# Sheet1.net
KiCad netlist of a schematic drawn in Altium Designer
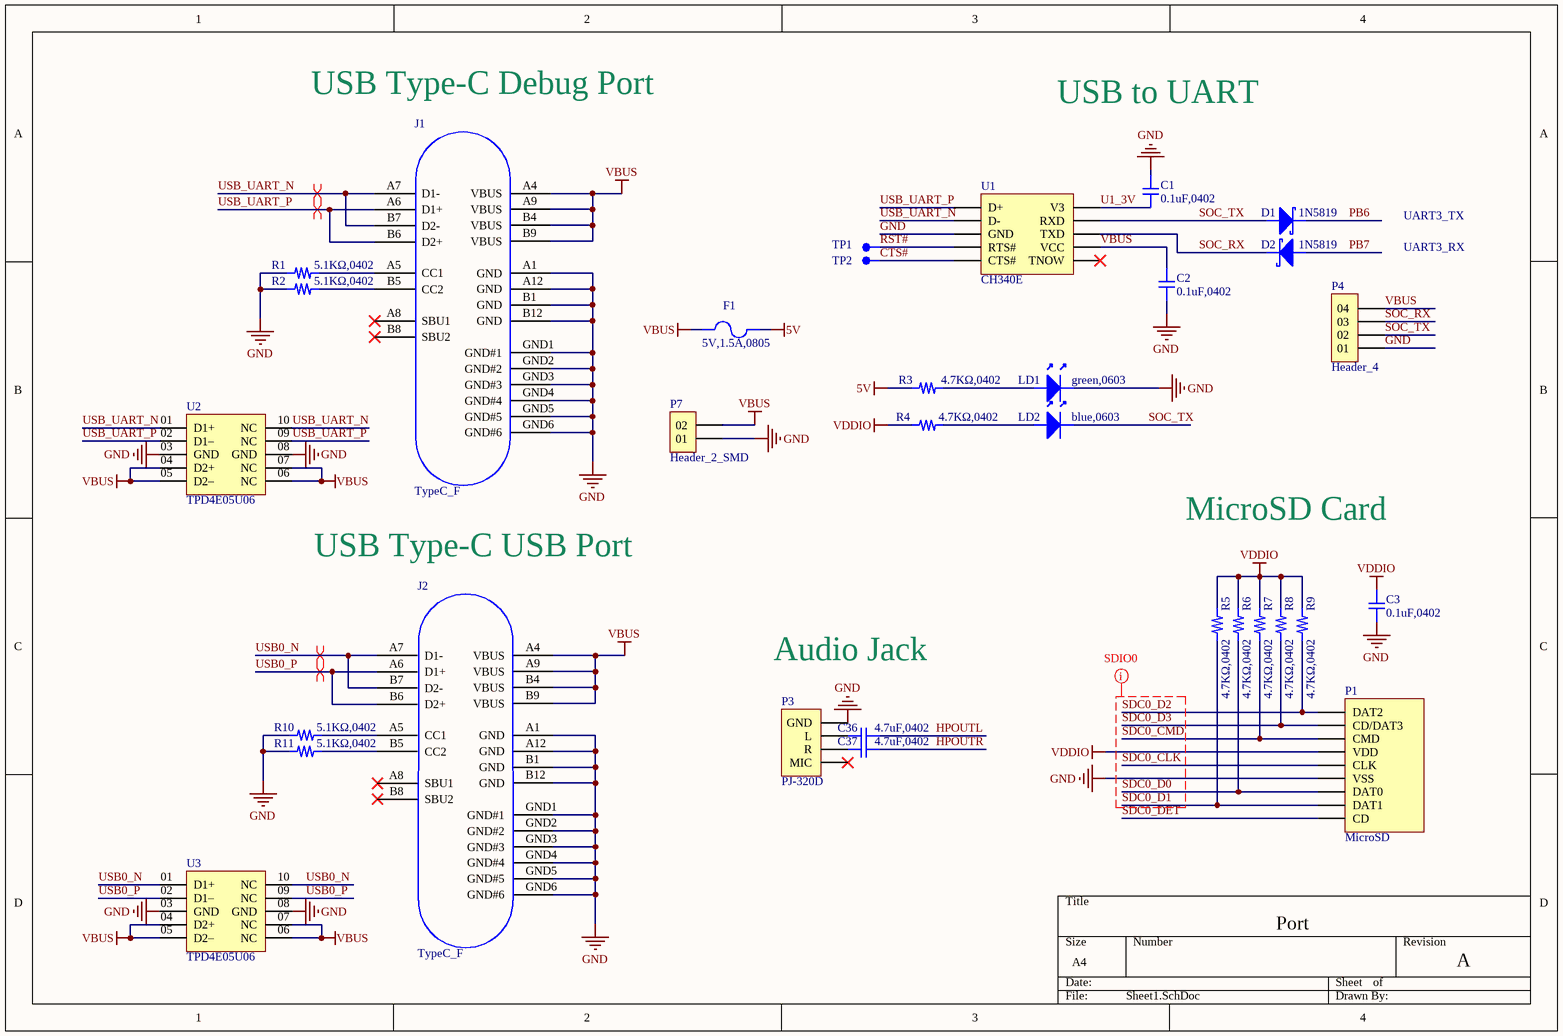
[diagram p0: Sheet1.SchDoc]

(export (version "E")
  (design (tool "Eeschema 10.0.6"))
  (components
    (comp (ref "C1") (value "0.1uF,0402") (footprint "C0402") (libsource (lib "myLib1") (part "Cap")))
    (comp (ref "C2") (value "0.1uF,0402") (footprint "C0402") (libsource (lib "myLib1") (part "Cap")))
    (comp (ref "C3") (value "0.1uF,0402") (footprint "C0402") (libsource (lib "myLib1") (part "Cap")))
    (comp (ref "C36") (value "4.7uF,0402") (footprint "C0402") (libsource (lib "myLib1") (part "Cap")))
    (comp (ref "C37") (value "4.7uF,0402") (footprint "C0402") (libsource (lib "myLib1") (part "Cap")))
    (comp (ref "D1")
      (value "1N5819")
      (footprint "SOD-323")
      (libsource (lib "myLib1") (part "Diode - Schottky"))
    )
    (comp (ref "D2")
      (value "1N5819")
      (footprint "SOD-323")
      (libsource (lib "myLib1") (part "Diode - Schottky"))
    )
    (comp (ref "F1") (value "5V,1.5A,0805") (footprint "F0805") (libsource (lib "myLib1") (part "Fuse")))
    (comp (ref "J1")
      (value "TypeC_F")
      (footprint "Type-C_16P_F_0.5_DIP")
      (description "Female SMD Connector")
      (libsource (lib "myLib1") (part "Type-C_16P_F_0.5"))
    )
    (comp (ref "J2")
      (value "TypeC_F")
      (footprint "Type-C_16P_F_0.5_DIP")
      (description "Female SMD Connector")
      (libsource (lib "myLib1") (part "Type-C_16P_F_0.5"))
    )
    (comp (ref "LD1")
      (value "green,0603")
      (footprint "LED0603")
      (libsource (lib "myLib1") (part "Diode - LED"))
    )
    (comp (ref "LD2")
      (value "blue,0603")
      (footprint "LED0603")
      (libsource (lib "myLib1") (part "Diode - LED"))
    )
    (comp (ref "P1") (value "MicroSD") (footprint "MicroSD") (libsource (lib "myLib1") (part "MicroSD")))
    (comp (ref "P3")
      (value "PJ-320D")
      (footprint "PJ-320D")
      (description "Audio jack")
      (libsource (lib "myLib1") (part "PJ-320D"))
    )
    (comp (ref "P4")
      (value "Header_4")
      (footprint "HEADER_4_SMD")
      (libsource (lib "myLib1") (part "Header_4"))
    )
    (comp (ref "P7")
      (value "Header_2_SMD")
      (footprint "HEADER_2_SMD")
      (libsource (lib "myLib1") (part "Header_2"))
    )
    (comp (ref "R1") (value "5.1KΩ,0402") (footprint "R0402") (libsource (lib "myLib1") (part "Res")))
    (comp (ref "R2") (value "5.1KΩ,0402") (footprint "R0402") (libsource (lib "myLib1") (part "Res")))
    (comp (ref "R3") (value "4.7KΩ,0402") (footprint "R0402") (libsource (lib "myLib1") (part "Res")))
    (comp (ref "R4") (value "4.7KΩ,0402") (footprint "R0402") (libsource (lib "myLib1") (part "Res")))
    (comp (ref "R5") (value "4.7KΩ,0402") (footprint "R0402") (libsource (lib "myLib1") (part "Res")))
    (comp (ref "R6") (value "4.7KΩ,0402") (footprint "R0402") (libsource (lib "myLib1") (part "Res")))
    (comp (ref "R7") (value "4.7KΩ,0402") (footprint "R0402") (libsource (lib "myLib1") (part "Res")))
    (comp (ref "R8") (value "4.7KΩ,0402") (footprint "R0402") (libsource (lib "myLib1") (part "Res")))
    (comp (ref "R9") (value "4.7KΩ,0402") (footprint "R0402") (libsource (lib "myLib1") (part "Res")))
    (comp (ref "R10") (value "5.1KΩ,0402") (footprint "R0402") (libsource (lib "myLib1") (part "Res")))
    (comp (ref "R11") (value "5.1KΩ,0402") (footprint "R0402") (libsource (lib "myLib1") (part "Res")))
    (comp (ref "TP1") (value "TP") (footprint "TP") (libsource (lib "myLib1") (part "TP")))
    (comp (ref "TP2") (value "TP") (footprint "TP") (libsource (lib "myLib1") (part "TP")))
    (comp (ref "U1") (value "CH340E") (footprint "MSOP-10") (libsource (lib "myLib1") (part "CH340E")))
    (comp (ref "U2")
      (value "TPD4E05U06")
      (footprint "USON-10")
      (libsource (lib "myLib1") (part "TPD4E05U06"))
    )
    (comp (ref "U3")
      (value "TPD4E05U06")
      (footprint "USON-10")
      (libsource (lib "myLib1") (part "TPD4E05U06"))
    )
  )
  (nets
    (net (code "1") (name "/CTS#") (class "Default")
      (node (ref "TP2") (pin "01") (pintype "passive"))
      (node (ref "U1") (pin "05") (pinfunction "CTS#_05") (pintype "passive"))
    )
    (net (code "2") (name "/HPOUTL") (class "Default") (node (ref "C36") (pin "01") (pintype "passive")))
    (net (code "3") (name "/HPOUTR") (class "Default") (node (ref "C37") (pin "01") (pintype "passive")))
    (net (code "4") (name "/PB6") (class "Default") (node (ref "D1") (pin "02") (pintype "passive")))
    (net (code "5") (name "/PB7") (class "Default") (node (ref "D2") (pin "01") (pintype "passive")))
    (net (code "6") (name "/RST#") (class "Default")
      (node (ref "TP1") (pin "01") (pintype "passive"))
      (node (ref "U1") (pin "04") (pinfunction "RTS#_04") (pintype "passive"))
    )
    (net (code "7") (name "/SDC0_CLK") (class "Default")
      (node (ref "P1") (pin "05") (pinfunction "CLK_05") (pintype "passive"))
    )
    (net (code "8") (name "/SDC0_CMD") (class "Default")
      (node (ref "P1") (pin "03") (pinfunction "CMD_03") (pintype "passive"))
      (node (ref "R7") (pin "01") (pintype "passive"))
    )
    (net (code "9") (name "/SDC0_D0") (class "Default")
      (node (ref "P1") (pin "07") (pinfunction "DAT0_07") (pintype "passive"))
      (node (ref "R6") (pin "01") (pintype "passive"))
    )
    (net (code "10") (name "/SDC0_D1") (class "Default")
      (node (ref "P1") (pin "08") (pinfunction "DAT1_08") (pintype "passive"))
      (node (ref "R5") (pin "01") (pintype "passive"))
    )
    (net (code "11") (name "/SDC0_D2") (class "Default")
      (node (ref "P1") (pin "01") (pinfunction "DAT2_01") (pintype "passive"))
      (node (ref "R9") (pin "01") (pintype "passive"))
    )
    (net (code "12") (name "/SDC0_D3") (class "Default")
      (node (ref "P1") (pin "02") (pinfunction "CD/DAT3_02") (pintype "passive"))
      (node (ref "R8") (pin "01") (pintype "passive"))
    )
    (net (code "13") (name "/SDC0_DET") (class "Default")
      (node (ref "P1") (pin "09") (pinfunction "CD_09") (pintype "passive"))
    )
    (net (code "14") (name "/SOC_RX") (class "Default")
      (node (ref "D2") (pin "02") (pintype "passive"))
      (node (ref "P4") (pin "03") (pinfunction "03_03") (pintype "passive"))
      (node (ref "U1") (pin "08") (pinfunction "TXD_08") (pintype "passive"))
    )
    (net (code "15") (name "/SOC_TX") (class "Default")
      (node (ref "D1") (pin "01") (pintype "passive"))
      (node (ref "LD2") (pin "02") (pintype "passive"))
      (node (ref "P4") (pin "02") (pinfunction "02_02") (pintype "passive"))
      (node (ref "U1") (pin "09") (pinfunction "RXD_09") (pintype "passive"))
    )
    (net (code "16") (name "/U1_3V") (class "Default")
      (node (ref "C1") (pin "01") (pintype "passive"))
      (node (ref "U1") (pin "10") (pinfunction "V3_10") (pintype "passive"))
    )
    (net (code "17") (name "/USB0_N") (class "Default")
      (node (ref "J2") (pin "A7") (pinfunction "D1-_A7") (pintype "passive"))
      (node (ref "J2") (pin "B7") (pinfunction "D2-_B7") (pintype "passive"))
      (node (ref "U3") (pin "01") (pinfunction "D1+_01") (pintype "passive"))
      (node (ref "U3") (pin "10") (pinfunction "NC_10") (pintype "passive"))
    )
    (net (code "18") (name "/USB0_P") (class "Default")
      (node (ref "J2") (pin "A6") (pinfunction "D1+_A6") (pintype "passive"))
      (node (ref "J2") (pin "B6") (pinfunction "D2+_B6") (pintype "passive"))
      (node (ref "U3") (pin "02") (pinfunction "D1–_02") (pintype "passive"))
      (node (ref "U3") (pin "09") (pinfunction "NC_09") (pintype "passive"))
    )
    (net (code "19") (name "/USB_UART_N") (class "Default")
      (node (ref "J1") (pin "A7") (pinfunction "D1-_A7") (pintype "passive"))
      (node (ref "J1") (pin "B7") (pinfunction "D2-_B7") (pintype "passive"))
      (node (ref "U1") (pin "02") (pinfunction "D-_02") (pintype "passive"))
      (node (ref "U2") (pin "01") (pinfunction "D1+_01") (pintype "passive"))
      (node (ref "U2") (pin "10") (pinfunction "NC_10") (pintype "passive"))
    )
    (net (code "20") (name "/USB_UART_P") (class "Default")
      (node (ref "J1") (pin "A6") (pinfunction "D1+_A6") (pintype "passive"))
      (node (ref "J1") (pin "B6") (pinfunction "D2+_B6") (pintype "passive"))
      (node (ref "U1") (pin "01") (pinfunction "D+_01") (pintype "passive"))
      (node (ref "U2") (pin "02") (pinfunction "D1–_02") (pintype "passive"))
      (node (ref "U2") (pin "09") (pinfunction "NC_09") (pintype "passive"))
    )
    (net (code "21") (name "5V") (class "Default")
      (node (ref "F1") (pin "02") (pintype "passive"))
      (node (ref "R3") (pin "01") (pintype "passive"))
    )
    (net (code "22") (name "GND") (class "Default")
      (node (ref "C1") (pin "02") (pintype "passive"))
      (node (ref "C2") (pin "01") (pintype "passive"))
      (node (ref "C3") (pin "01") (pintype "passive"))
      (node (ref "J1") (pin "A1") (pinfunction "GND_A1") (pintype "power_in"))
      (node (ref "J1") (pin "A12") (pinfunction "GND_A12") (pintype "power_in"))
      (node (ref "J1") (pin "B1") (pinfunction "GND_B1") (pintype "power_in"))
      (node (ref "J1") (pin "B12") (pinfunction "GND_B12") (pintype "power_in"))
      (node (ref "J1") (pin "GND1") (pinfunction "GND#1_GND1") (pintype "passive"))
      (node (ref "J1") (pin "GND2") (pinfunction "GND#2_GND2") (pintype "passive"))
      (node (ref "J1") (pin "GND3") (pinfunction "GND#3_GND3") (pintype "passive"))
      (node (ref "J1") (pin "GND4") (pinfunction "GND#4_GND4") (pintype "passive"))
      (node (ref "J1") (pin "GND5") (pinfunction "GND#5_GND5") (pintype "passive"))
      (node (ref "J1") (pin "GND6") (pinfunction "GND#6_GND6") (pintype "passive"))
      (node (ref "J2") (pin "A1") (pinfunction "GND_A1") (pintype "power_in"))
      (node (ref "J2") (pin "A12") (pinfunction "GND_A12") (pintype "power_in"))
      (node (ref "J2") (pin "B1") (pinfunction "GND_B1") (pintype "power_in"))
      (node (ref "J2") (pin "B12") (pinfunction "GND_B12") (pintype "power_in"))
      (node (ref "J2") (pin "GND1") (pinfunction "GND#1_GND1") (pintype "passive"))
      (node (ref "J2") (pin "GND2") (pinfunction "GND#2_GND2") (pintype "passive"))
      (node (ref "J2") (pin "GND3") (pinfunction "GND#3_GND3") (pintype "passive"))
      (node (ref "J2") (pin "GND4") (pinfunction "GND#4_GND4") (pintype "passive"))
      (node (ref "J2") (pin "GND5") (pinfunction "GND#5_GND5") (pintype "passive"))
      (node (ref "J2") (pin "GND6") (pinfunction "GND#6_GND6") (pintype "passive"))
      (node (ref "LD1") (pin "02") (pintype "passive"))
      (node (ref "P1") (pin "06") (pinfunction "VSS_06") (pintype "passive"))
      (node (ref "P3") (pin "01") (pinfunction "GND_01") (pintype "passive"))
      (node (ref "P4") (pin "01") (pinfunction "01_01") (pintype "passive"))
      (node (ref "P7") (pin "01") (pinfunction "01_01") (pintype "passive"))
      (node (ref "R1") (pin "01") (pintype "passive"))
      (node (ref "R10") (pin "01") (pintype "passive"))
      (node (ref "R11") (pin "01") (pintype "passive"))
      (node (ref "R2") (pin "01") (pintype "passive"))
      (node (ref "U1") (pin "03") (pinfunction "GND_03") (pintype "passive"))
      (node (ref "U2") (pin "03") (pinfunction "GND_03") (pintype "passive"))
      (node (ref "U2") (pin "08") (pinfunction "GND_08") (pintype "passive"))
      (node (ref "U3") (pin "03") (pinfunction "GND_03") (pintype "passive"))
      (node (ref "U3") (pin "08") (pinfunction "GND_08") (pintype "passive"))
    )
    (net (code "23") (name "Net-(J1-CC1)") (class "Default")
      (node (ref "J1") (pin "A5") (pinfunction "CC1_A5") (pintype "passive"))
      (node (ref "R1") (pin "02") (pintype "passive"))
    )
    (net (code "24") (name "Net-(J1-CC2)") (class "Default")
      (node (ref "J1") (pin "B5") (pinfunction "CC2_B5") (pintype "passive"))
      (node (ref "R2") (pin "02") (pintype "passive"))
    )
    (net (code "25") (name "Net-(J2-CC1)") (class "Default")
      (node (ref "J2") (pin "A5") (pinfunction "CC1_A5") (pintype "passive"))
      (node (ref "R10") (pin "02") (pintype "passive"))
    )
    (net (code "26") (name "Net-(J2-CC2)") (class "Default")
      (node (ref "J2") (pin "B5") (pinfunction "CC2_B5") (pintype "passive"))
      (node (ref "R11") (pin "02") (pintype "passive"))
    )
    (net (code "27") (name "Net-(LD1-Pad01)") (class "Default")
      (node (ref "LD1") (pin "01") (pintype "passive"))
      (node (ref "R3") (pin "02") (pintype "passive"))
    )
    (net (code "28") (name "Net-(LD2-Pad01)") (class "Default")
      (node (ref "LD2") (pin "01") (pintype "passive"))
      (node (ref "R4") (pin "02") (pintype "passive"))
    )
    (net (code "29") (name "Net-(P3-L)") (class "Default")
      (node (ref "C36") (pin "02") (pintype "passive"))
      (node (ref "P3") (pin "04") (pinfunction "L_04") (pintype "passive"))
    )
    (net (code "30") (name "Net-(P3-R)") (class "Default")
      (node (ref "C37") (pin "02") (pintype "passive"))
      (node (ref "P3") (pin "03") (pinfunction "R_03") (pintype "passive"))
    )
    (net (code "31") (name "VBUS") (class "Default")
      (node (ref "C2") (pin "02") (pintype "passive"))
      (node (ref "F1") (pin "01") (pintype "passive"))
      (node (ref "J1") (pin "A4") (pinfunction "VBUS_A4") (pintype "power_in"))
      (node (ref "J1") (pin "A9") (pinfunction "VBUS_A9") (pintype "power_in"))
      (node (ref "J1") (pin "B4") (pinfunction "VBUS_B4") (pintype "power_in"))
      (node (ref "J1") (pin "B9") (pinfunction "VBUS_B9") (pintype "power_in"))
      (node (ref "J2") (pin "A4") (pinfunction "VBUS_A4") (pintype "power_in"))
      (node (ref "J2") (pin "A9") (pinfunction "VBUS_A9") (pintype "power_in"))
      (node (ref "J2") (pin "B4") (pinfunction "VBUS_B4") (pintype "power_in"))
      (node (ref "J2") (pin "B9") (pinfunction "VBUS_B9") (pintype "power_in"))
      (node (ref "P4") (pin "04") (pinfunction "04_04") (pintype "passive"))
      (node (ref "P7") (pin "02") (pinfunction "02_02") (pintype "passive"))
      (node (ref "U1") (pin "07") (pinfunction "VCC_07") (pintype "passive"))
      (node (ref "U2") (pin "04") (pinfunction "D2+_04") (pintype "passive"))
      (node (ref "U2") (pin "05") (pinfunction "D2–_05") (pintype "passive"))
      (node (ref "U2") (pin "06") (pinfunction "NC_06") (pintype "passive"))
      (node (ref "U2") (pin "07") (pinfunction "NC_07") (pintype "passive"))
      (node (ref "U3") (pin "04") (pinfunction "D2+_04") (pintype "passive"))
      (node (ref "U3") (pin "05") (pinfunction "D2–_05") (pintype "passive"))
      (node (ref "U3") (pin "06") (pinfunction "NC_06") (pintype "passive"))
      (node (ref "U3") (pin "07") (pinfunction "NC_07") (pintype "passive"))
    )
    (net (code "32") (name "VDDIO") (class "Default")
      (node (ref "C3") (pin "02") (pintype "passive"))
      (node (ref "P1") (pin "04") (pinfunction "VDD_04") (pintype "passive"))
      (node (ref "R4") (pin "01") (pintype "passive"))
      (node (ref "R5") (pin "02") (pintype "passive"))
      (node (ref "R6") (pin "02") (pintype "passive"))
      (node (ref "R7") (pin "02") (pintype "passive"))
      (node (ref "R8") (pin "02") (pintype "passive"))
      (node (ref "R9") (pin "02") (pintype "passive"))
    )
    (net (code "33") (name "unconnected-(J1-SBU1-PadA8)") (class "Default")
      (node (ref "J1") (pin "A8") (pinfunction "SBU1_A8") (pintype "passive+no_connect"))
    )
    (net (code "34") (name "unconnected-(J1-SBU2-PadB8)") (class "Default")
      (node (ref "J1") (pin "B8") (pinfunction "SBU2_B8") (pintype "passive+no_connect"))
    )
    (net (code "35") (name "unconnected-(J2-SBU1-PadA8)") (class "Default")
      (node (ref "J2") (pin "A8") (pinfunction "SBU1_A8") (pintype "passive+no_connect"))
    )
    (net (code "36") (name "unconnected-(J2-SBU2-PadB8)") (class "Default")
      (node (ref "J2") (pin "B8") (pinfunction "SBU2_B8") (pintype "passive+no_connect"))
    )
    (net (code "37") (name "unconnected-(P3-MIC-Pad02)") (class "Default")
      (node (ref "P3") (pin "02") (pinfunction "MIC_02") (pintype "passive+no_connect"))
    )
    (net (code "38") (name "unconnected-(U1-TNOW-Pad06)") (class "Default")
      (node (ref "U1") (pin "06") (pinfunction "TNOW_06") (pintype "passive+no_connect"))
    )
  )
)
